# MotorCANInterface.net
KiCad netlist of a schematic drawn in Altium Designer
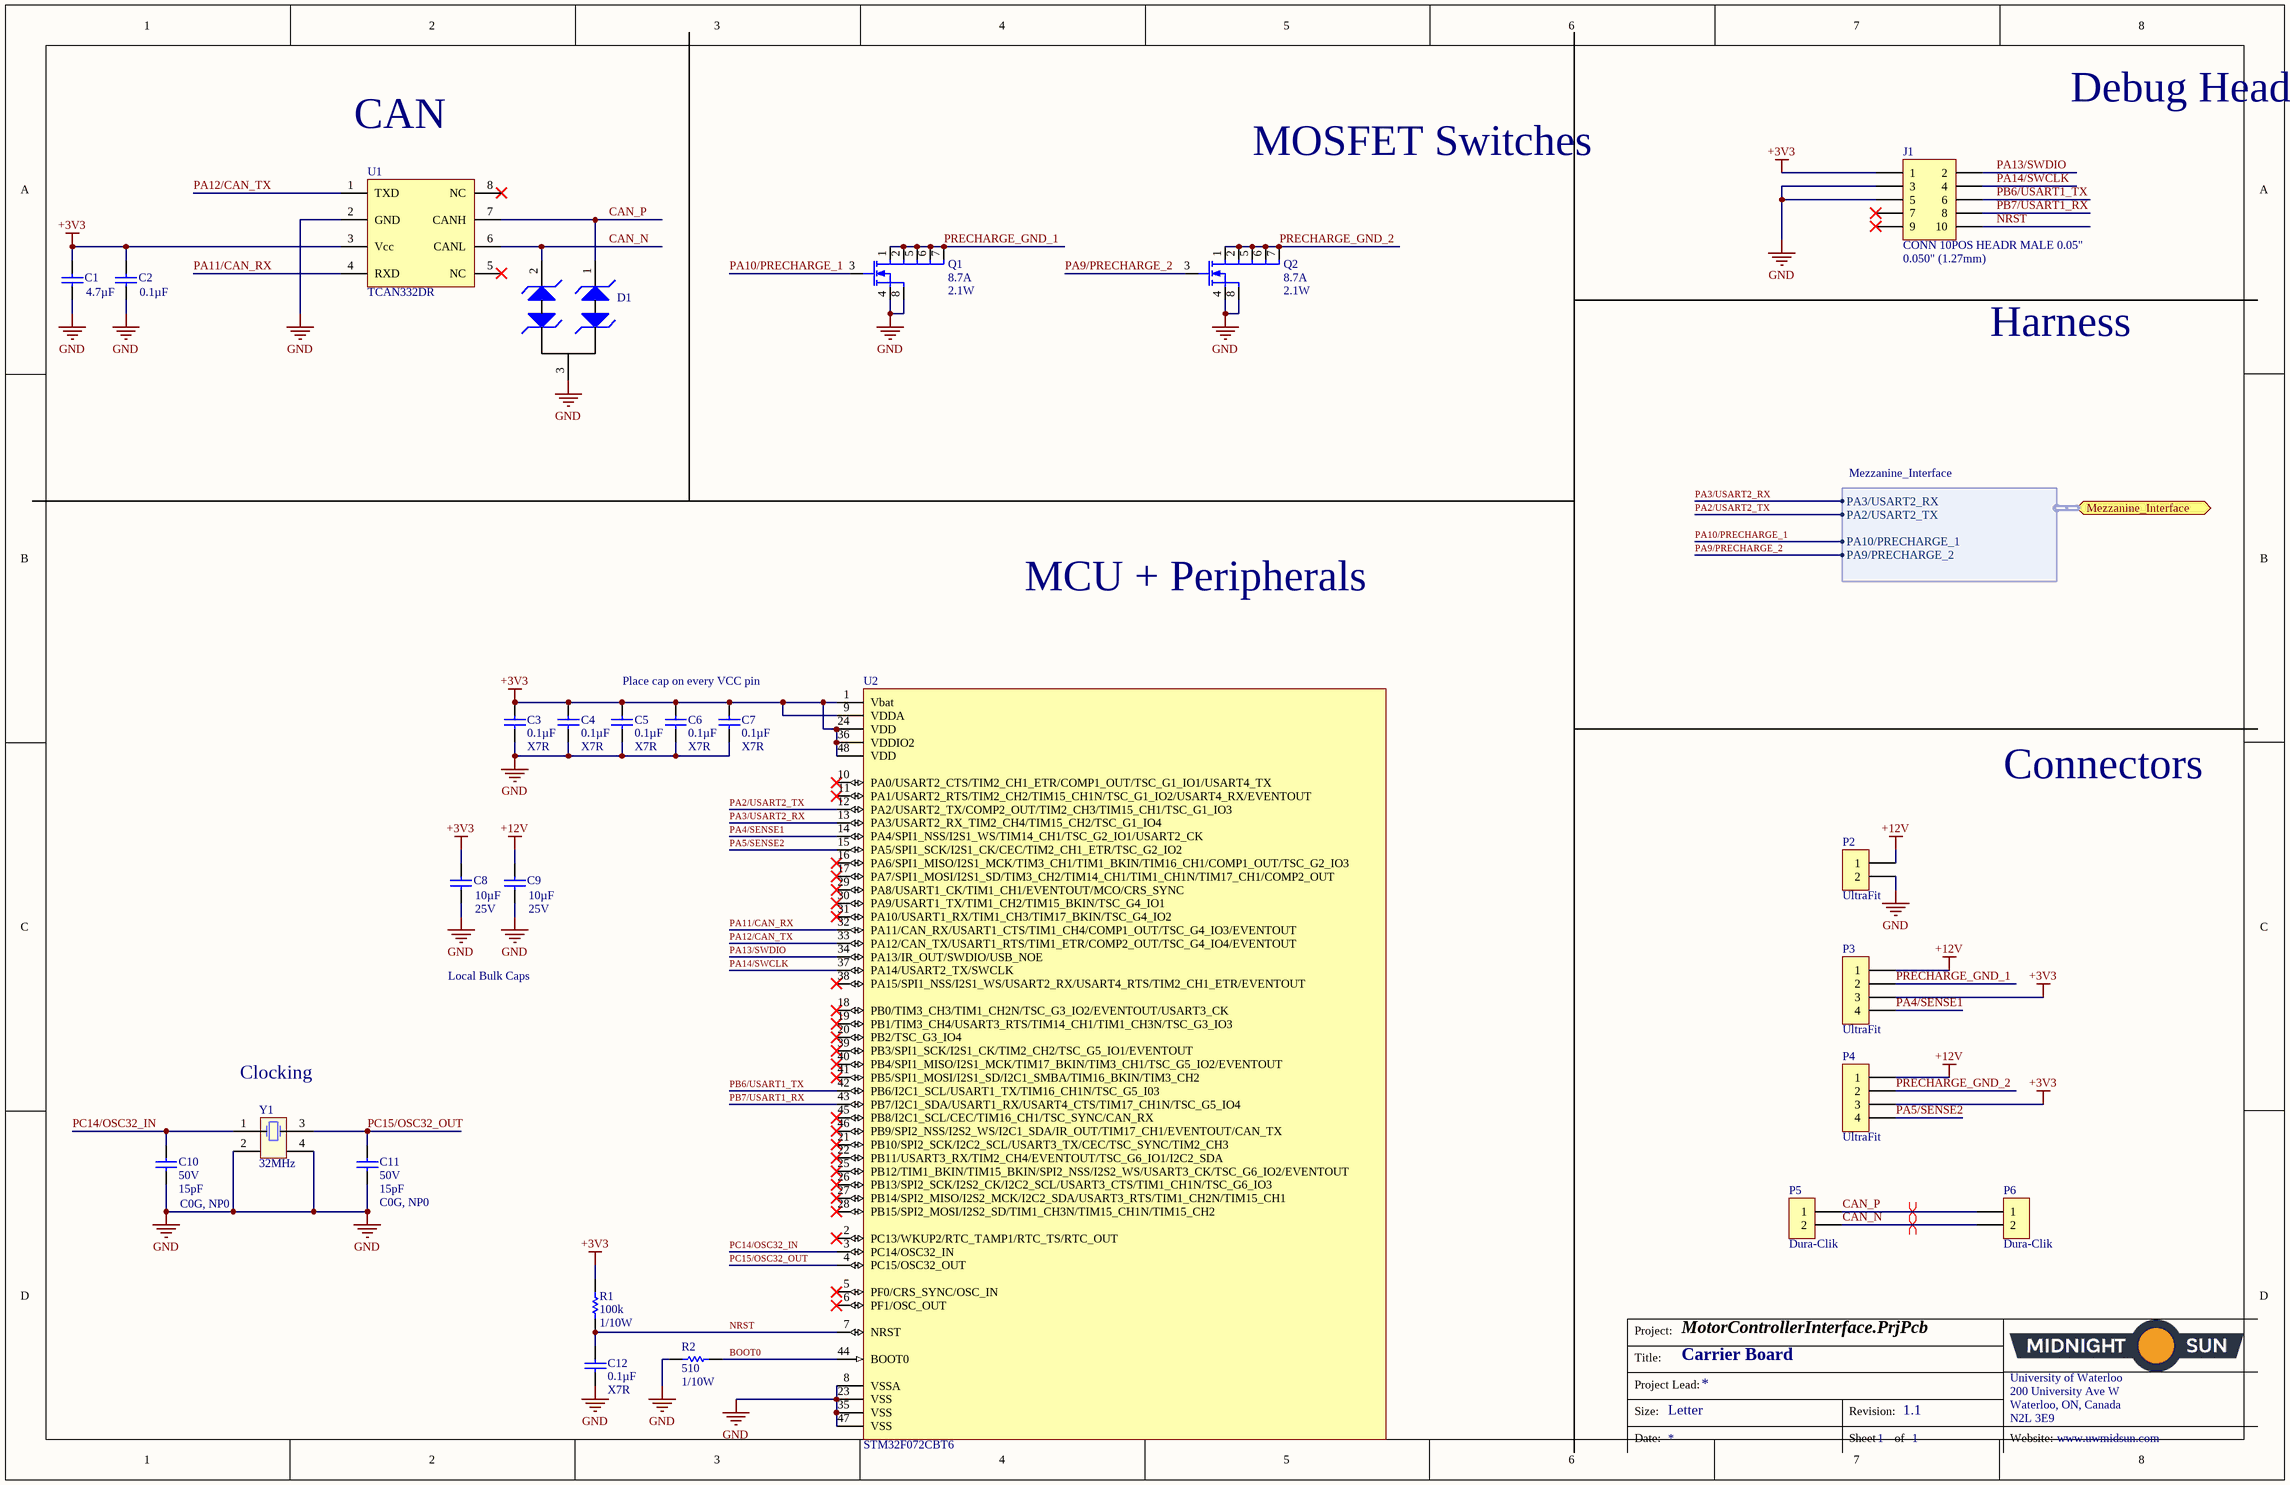
[diagram p0: MotorCANInterface.SchDoc]

(export (version "E")
  (design (tool "Eeschema 10.0.6"))
  (components
    (comp (ref "C1")
      (value "CAP CER 4.7UF 25V 10% X5R 0603")
      (footprint "CAP, 0603")
      (description "4.7µF ±10% 25V Ceramic Capacitor X5R 0603 (1608 Metric)")
      (fields
        (field (name "VOLTAGE") "25V")
        (field (name "TOLERANCE") "±10%")
        (field (name "CAPACITANCE") "4.7µF")
      )
      (libsource (lib "Schematic Diagrams") (part "CAP CER 4.7UF 25V 10% X5R 0603"))
    )
    (comp (ref "C2")
      (value "CAP CER 0.1UF 50V 10% X7R 0603")
      (footprint "CAP, 0603")
      (description "0.10µF ±10% 50V Ceramic Capacitor X7R 0603 (1608 Metric)")
      (fields
        (field (name "VOLTAGE") "50V")
        (field (name "TOLERANCE") "±10%")
        (field (name "CAPACITANCE") "0.1µF")
      )
      (libsource (lib "Schematic Diagrams") (part "CAP CER 0.1UF 50V 10% X7R 0603"))
    )
    (comp (ref "C3")
      (value "CAP CER 0.1UF 50V 10% X7R 0603")
      (footprint "CAP, 0603")
      (description "0.10µF ±10% 50V Ceramic Capacitor X7R 0603 (1608 Metric)")
      (fields
        (field (name "VOLTAGE") "50V")
        (field (name "TOLERANCE") "±10%")
        (field (name "CAPACITANCE") "0.1µF")
        (field (name "TEMPERATURE COEFFICIENT") "X7R")
      )
      (libsource (lib "Schematic Diagrams") (part "CAP CER 0.1UF 50V 10% X7R 0603"))
    )
    (comp (ref "C4")
      (value "CAP CER 0.1UF 50V 10% X7R 0603")
      (footprint "CAP, 0603")
      (description "0.10µF ±10% 50V Ceramic Capacitor X7R 0603 (1608 Metric)")
      (fields
        (field (name "VOLTAGE") "50V")
        (field (name "TOLERANCE") "±10%")
        (field (name "CAPACITANCE") "0.1µF")
        (field (name "TEMPERATURE COEFFICIENT") "X7R")
      )
      (libsource (lib "Schematic Diagrams") (part "CAP CER 0.1UF 50V 10% X7R 0603"))
    )
    (comp (ref "C5")
      (value "CAP CER 0.1UF 50V 10% X7R 0603")
      (footprint "CAP, 0603")
      (description "0.10µF ±10% 50V Ceramic Capacitor X7R 0603 (1608 Metric)")
      (fields
        (field (name "VOLTAGE") "50V")
        (field (name "TOLERANCE") "±10%")
        (field (name "CAPACITANCE") "0.1µF")
        (field (name "TEMPERATURE COEFFICIENT") "X7R")
      )
      (libsource (lib "Schematic Diagrams") (part "CAP CER 0.1UF 50V 10% X7R 0603"))
    )
    (comp (ref "C6")
      (value "CAP CER 0.1UF 50V 10% X7R 0603")
      (footprint "CAP, 0603")
      (description "0.10µF ±10% 50V Ceramic Capacitor X7R 0603 (1608 Metric)")
      (fields
        (field (name "VOLTAGE") "50V")
        (field (name "TOLERANCE") "±10%")
        (field (name "CAPACITANCE") "0.1µF")
        (field (name "TEMPERATURE COEFFICIENT") "X7R")
      )
      (libsource (lib "Schematic Diagrams") (part "CAP CER 0.1UF 50V 10% X7R 0603"))
    )
    (comp (ref "C7")
      (value "CAP CER 0.1UF 50V 10% X7R 0603")
      (footprint "CAP, 0603")
      (description "0.10µF ±10% 50V Ceramic Capacitor X7R 0603 (1608 Metric)")
      (fields
        (field (name "VOLTAGE") "50V")
        (field (name "TOLERANCE") "±10%")
        (field (name "CAPACITANCE") "0.1µF")
        (field (name "TEMPERATURE COEFFICIENT") "X7R")
      )
      (libsource (lib "Schematic Diagrams") (part "CAP CER 0.1UF 50V 10% X7R 0603"))
    )
    (comp (ref "C8")
      (value "CAP CER 10uF 25V 10% X5R 0805")
      (footprint "CAP, 0805")
      (description "10µF ±10% 25V Ceramic Capacitor X5R 0805 (2012 Metric)")
      (fields
        (field (name "MANUFACTURER") "Murata Electronics North America")
        (field (name "MANUFACTURER PART NUMBER") "GRM21BR61E106KA73L")
        (field (name "VOLTAGE - RATED") "25V")
        (field (name "CAPACITANCE") "10µF")
      )
      (libsource (lib "Schematic Diagrams") (part "CAP CER 10uF 25V 10% X5R 0805"))
    )
    (comp (ref "C9")
      (value "CAP CER 10uF 25V 10% X5R 0805")
      (footprint "CAP, 0805")
      (description "10µF ±10% 25V Ceramic Capacitor X5R 0805 (2012 Metric)")
      (fields
        (field (name "MANUFACTURER") "Murata Electronics North America")
        (field (name "MANUFACTURER PART NUMBER") "GRM21BR61E106KA73L")
        (field (name "VOLTAGE - RATED") "25V")
        (field (name "CAPACITANCE") "10µF")
      )
      (libsource (lib "Schematic Diagrams") (part "CAP CER 10uF 25V 10% X5R 0805"))
    )
    (comp (ref "C10")
      (value "CAP CER 15PF 50V ±5% NPO 0603")
      (footprint "CAP, 0603")
      (description "15pF ±5% 50V Ceramic Capacitor C0G, NP0 0603 (1608 Metric)")
      (fields
        (field (name "VOLTAGE") "50V")
        (field (name "TOLERANCE") "±5%")
        (field (name "CAPACITANCE") "15pF")
        (field (name "TEMPERATURE COEFFICIENT") "C0G, NP0")
      )
      (libsource (lib "Schematic Diagrams") (part "CAP CER 15PF 50V ±5% NPO 0603"))
    )
    (comp (ref "C11")
      (value "CAP CER 15PF 50V ±5% NPO 0603")
      (footprint "CAP, 0603")
      (description "15pF ±5% 50V Ceramic Capacitor C0G, NP0 0603 (1608 Metric)")
      (fields
        (field (name "VOLTAGE") "50V")
        (field (name "TOLERANCE") "±5%")
        (field (name "CAPACITANCE") "15pF")
        (field (name "TEMPERATURE COEFFICIENT") "C0G, NP0")
      )
      (libsource (lib "Schematic Diagrams") (part "CAP CER 15PF 50V ±5% NPO 0603"))
    )
    (comp (ref "C12")
      (value "CAP CER 0.1UF 50V 10% X7R 0603")
      (footprint "CAP, 0603")
      (description "0.10µF ±10% 50V Ceramic Capacitor X7R 0603 (1608 Metric)")
      (fields
        (field (name "VOLTAGE") "50V")
        (field (name "TOLERANCE") "±10%")
        (field (name "CAPACITANCE") "0.1µF")
        (field (name "TEMPERATURE COEFFICIENT") "X7R")
      )
      (libsource (lib "Schematic Diagrams") (part "CAP CER 0.1UF 50V 10% X7R 0603"))
    )
    (comp (ref "D1")
      (value "DIODE TVS 24VWM 70VC SOT23")
      (footprint "SOT23")
      (description "TVS DIODE 24VWM 70VC SOT23")
      (libsource (lib "Schematic Diagrams") (part "DIODE TVS 24VWM 70VC SOT23"))
    )
    (comp (ref "J1")
      (value "CONN 10POS HEADR MALE 0.05\"")
      (footprint "CONN, 10POS 0.05\" Debug Header")
      (description "10 Positions Header Connector 0.050\" (1.27mm) Surface Mount Gold")
      (fields (field (name "PITCH - MATING") "0.050\" (1.27mm)"))
      (libsource (lib "Schematic Diagrams") (part "CONN 10POS HEADR MALE 0.05{dblquote}"))
    )
    (comp (ref "P2")
      (value "CONN 2POS ULTRA-FIT 0.138\"")
      (footprint "CONN, 2POS ULTRA-FIT")
      (description "2 Positions Header, Shrouded Connector 0.138\" (3.50mm) Through Hole Gold")
      (fields (field (name "VOLTAGE") "400V") (field (name "SERIES") "UltraFit"))
      (libsource (lib "Schematic Diagrams") (part "CONN 2POS ULTRA-FIT 0.138{dblquote}"))
    )
    (comp (ref "P3")
      (value "CONN 4POS ULTRA-FIT 0.138\"")
      (footprint "CONN, 4POS ULTRA-FIT")
      (description "4 Positions Header Connector 0.138\" (3.50mm) Through Hole Tin")
      (fields (field (name "VOLTAGE") "400V") (field (name "SERIES") "UltraFit"))
      (libsource (lib "Schematic Diagrams") (part "CONN 4POS ULTRA-FIT 0.138{dblquote}"))
    )
    (comp (ref "P4")
      (value "CONN 4POS ULTRA-FIT 0.138\"")
      (footprint "CONN, 4POS ULTRA-FIT")
      (description "4 Positions Header Connector 0.138\" (3.50mm) Through Hole Tin")
      (fields (field (name "VOLTAGE") "400V") (field (name "SERIES") "UltraFit"))
      (libsource (lib "Schematic Diagrams") (part "CONN 4POS ULTRA-FIT 0.138{dblquote}"))
    )
    (comp (ref "P5")
      (value "Dura-Clik")
      (footprint "CONN, 2POS Dura-Click Vertical")
      (description "2 Positions Header, Shrouded Connector 0.079\" (2.00mm) Surface Mount, Vertical Tin")
      (fields
        (field (name "MANUFACTURER") "Molex, LLC")
        (field (name "MANUFACTURER PART NUMBER") "5600200220")
      )
      (libsource (lib "") (part "CONN 2POS DURA-CLIK 0.079{dblquote} VERT_1"))
    )
    (comp (ref "P6")
      (value "Dura-Clik")
      (footprint "CONN, 2POS Dura-Click Vertical")
      (description "2 Positions Header, Shrouded Connector 0.079\" (2.00mm) Surface Mount, Vertical Tin")
      (fields
        (field (name "MANUFACTURER") "Molex, LLC")
        (field (name "MANUFACTURER PART NUMBER") "5600200220")
      )
      (libsource (lib "Schematic Diagrams") (part "CONN 2POS DURA-CLIK 0.079{dblquote} VERT"))
    )
    (comp (ref "Q1")
      (value "MOSFET N-CH 30V 8.7A 2.1W 6-PQFN (2x2)")
      (footprint "MOSFET N-CH 30V 12A 2mmx2mm PQFN")
      (fields
        (field (name "CURRENT - CONTINUOUS DRAIN (ID) @ 25°C") "8.7A")
        (field (name "POWER DISSIPATION (MAX)") "2.1W")
      )
      (libsource (lib "Schematic Diagrams") (part "MOSFET N-CH 30V 8.7A 2.1W 6-PQFN (2x2)"))
    )
    (comp (ref "Q2")
      (value "MOSFET N-CH 30V 8.7A 2.1W 6-PQFN (2x2)")
      (footprint "MOSFET N-CH 30V 12A 2mmx2mm PQFN")
      (fields
        (field (name "CURRENT - CONTINUOUS DRAIN (ID) @ 25°C") "8.7A")
        (field (name "POWER DISSIPATION (MAX)") "2.1W")
      )
      (libsource (lib "Schematic Diagrams") (part "MOSFET N-CH 30V 8.7A 2.1W 6-PQFN (2x2)"))
    )
    (comp (ref "R1")
      (value "RES 100K OHM 5% 1/8W 0603")
      (footprint "RES, 0603")
      (description "RES SMD 100K OHM 5% 1/10W 0603")
      (fields
        (field (name "TOLERANCE") "±5%")
        (field (name "RESISTANCE") "100k")
        (field (name "POWER") "1/10W")
      )
      (libsource (lib "Schematic Diagrams") (part "RES 100K OHM 5% 1/8W 0603"))
    )
    (comp (ref "R2")
      (value "RES 510 OHM 5% 1/10W 0603")
      (footprint "RES, 0603")
      (description "RES SMD 510 OHM 5% 1/10W 0603")
      (fields
        (field (name "TOLERANCE") "±5%")
        (field (name "RESISTANCE") "510")
        (field (name "POWER") "1/10W")
      )
      (libsource (lib "Schematic Diagrams") (part "RES 510 OHM 5% 1/10W 0603"))
    )
    (comp (ref "U1")
      (value "IC CAN Tranceiver TCAN332DR")
      (footprint "TSOP65P280X145-8N")
      (description "1/1 Transceiver CAN 8-SOIC")
      (fields
        (field (name "DIGIKEY PART NUMBER") "296-43711-1-ND")
        (field (name "MANUFACTURER PART NUMBER") "TCAN332DR")
      )
      (libsource (lib "Schematic Diagrams") (part "IC CAN Tranceiver TCAN332DR"))
    )
    (comp (ref "U2")
      (value "IC MCU 32BIT 128KB FLASH 48LQFP")
      (footprint "TSQFP50P890X890X160-48M")
      (description "ARM® Cortex®-M0 STM32 F0 Microcontroller IC 32-Bit 48MHz 128KB (128K x 8) FLASH 48-LQFP (7x7)")
      (fields (field (name "MANUFACTURER PART NUMBER 1") "STM32F072CBT6"))
      (libsource (lib "Schematic Diagrams") (part "IC MCU 32BIT 128KB FLASH 48LQFP"))
    )
    (comp (ref "Y1")
      (value "CRYSTAL 32 MHz 8pF 4-SMD")
      (footprint "CX2520DB CRYSTAL")
      (description "32MHz ±15ppm Crystal 8pF 50 Ohm -40°C ~ 85°C AEC-Q200 Surface Mount 4-SMD, No Lead")
      (fields (field (name "FREQUENCY") "32MHz"))
      (libsource (lib "Schematic Diagrams") (part "CRYSTAL 32 MHz 8pF 4-SMD"))
    )
  )
  (nets
    (net (code "2") (name "+3V3") (class "Default")
      (node (ref "C1") (pin "1") (pinfunction "1_1") (pintype "passive"))
      (node (ref "C2") (pin "1") (pinfunction "1_1") (pintype "passive"))
      (node (ref "C3") (pin "1") (pinfunction "1_1") (pintype "passive"))
      (node (ref "C4") (pin "1") (pinfunction "1_1") (pintype "passive"))
      (node (ref "C5") (pin "1") (pinfunction "1_1") (pintype "passive"))
      (node (ref "C6") (pin "1") (pinfunction "1_1") (pintype "passive"))
      (node (ref "C7") (pin "1") (pinfunction "1_1") (pintype "passive"))
      (node (ref "C8") (pin "1") (pinfunction "1_1") (pintype "passive"))
      (node (ref "J1") (pin "1") (pinfunction "1_1") (pintype "passive"))
      (node (ref "P3") (pin "3") (pinfunction "3_3") (pintype "passive"))
      (node (ref "P4") (pin "3") (pinfunction "3_3") (pintype "passive"))
      (node (ref "R1") (pin "1") (pinfunction "1_1") (pintype "passive"))
      (node (ref "U1") (pin "3") (pinfunction "Vcc_3") (pintype "passive"))
      (node (ref "U2") (pin "1") (pinfunction "Vbat_1") (pintype "power_in"))
      (node (ref "U2") (pin "24") (pinfunction "VDD_24") (pintype "power_in"))
      (node (ref "U2") (pin "36") (pinfunction "VDDIO2_36") (pintype "power_in"))
      (node (ref "U2") (pin "48") (pinfunction "VDD_48") (pintype "power_in"))
      (node (ref "U2") (pin "9") (pinfunction "VDDA_9") (pintype "power_in"))
    )
    (net (code "3") (name "+12V") (class "Default")
      (node (ref "C9") (pin "1") (pinfunction "1_1") (pintype "passive"))
      (node (ref "P2") (pin "1") (pinfunction "1_1") (pintype "passive"))
      (node (ref "P3") (pin "1") (pinfunction "1_1") (pintype "passive"))
      (node (ref "P4") (pin "1") (pinfunction "1_1") (pintype "passive"))
    )
    (net (code "4") (name "/BOOT0") (class "Default")
      (node (ref "R2") (pin "2") (pinfunction "2_2") (pintype "passive"))
      (node (ref "U2") (pin "44") (pinfunction "BOOT0_44") (pintype "input"))
    )
    (net (code "5") (name "/CAN_N") (class "Default")
      (node (ref "D1") (pin "2") (pinfunction "Cathode2_2") (pintype "passive"))
      (node (ref "P5") (pin "2") (pinfunction "2_2") (pintype "passive"))
      (node (ref "P6") (pin "2") (pinfunction "2_2") (pintype "passive"))
      (node (ref "U1") (pin "6") (pinfunction "CANL_6") (pintype "passive"))
    )
    (net (code "6") (name "/CAN_P") (class "Default")
      (node (ref "D1") (pin "1") (pinfunction "Cathode1_1") (pintype "passive"))
      (node (ref "P5") (pin "1") (pinfunction "1_1") (pintype "passive"))
      (node (ref "P6") (pin "1") (pinfunction "1_1") (pintype "passive"))
      (node (ref "U1") (pin "7") (pinfunction "CANH_7") (pintype "passive"))
    )
    (net (code "7") (name "/NRST") (class "Default")
      (node (ref "C12") (pin "1") (pinfunction "1_1") (pintype "passive"))
      (node (ref "J1") (pin "10") (pinfunction "10_10") (pintype "passive"))
      (node (ref "R1") (pin "2") (pinfunction "2_2") (pintype "passive"))
      (node (ref "U2") (pin "7") (pinfunction "NRST_7") (pintype "bidirectional"))
    )
    (net (code "8") (name "/PA2{slash}USART2_TX") (class "Default")
      (node (ref "U2") (pin "12") (pinfunction "PA2/USART2_TX/COMP2_OUT/TIM2_CH3/TIM15_CH1/TSC_G1_IO3_12") (pintype "bidirectional"))
    )
    (net (code "9") (name "/PA3{slash}USART2_RX") (class "Default")
      (node (ref "U2") (pin "13") (pinfunction "PA3/USART2_RX_TIM2_CH4/TIM15_CH2/TSC_G1_IO4_13") (pintype "bidirectional"))
    )
    (net (code "10") (name "/PA4{slash}SENSE1") (class "Default")
      (node (ref "P3") (pin "4") (pinfunction "4_4") (pintype "passive"))
      (node (ref "U2") (pin "14") (pinfunction "PA4/SPI1_NSS/I2S1_WS/TIM14_CH1/TSC_G2_IO1/USART2_CK_14") (pintype "bidirectional"))
    )
    (net (code "11") (name "/PA5{slash}SENSE2") (class "Default")
      (node (ref "P4") (pin "4") (pinfunction "4_4") (pintype "passive"))
      (node (ref "U2") (pin "15") (pinfunction "PA5/SPI1_SCK/I2S1_CK/CEC/TIM2_CH1_ETR/TSC_G2_IO2_15") (pintype "bidirectional"))
    )
    (net (code "12") (name "/PA9{slash}PRECHARGE_2") (class "Default")
      (node (ref "Q2") (pin "3") (pinfunction "G_3") (pintype "passive"))
    )
    (net (code "13") (name "/PA10{slash}PRECHARGE_1") (class "Default")
      (node (ref "Q1") (pin "3") (pinfunction "G_3") (pintype "passive"))
    )
    (net (code "14") (name "/PA11{slash}CAN_RX") (class "Default")
      (node (ref "U1") (pin "4") (pinfunction "RXD_4") (pintype "passive"))
      (node (ref "U2") (pin "32") (pinfunction "PA11/CAN_RX/USART1_CTS/TIM1_CH4/COMP1_OUT/TSC_G4_IO3/EVENTOUT_32") (pintype "bidirectional"))
    )
    (net (code "15") (name "/PA12{slash}CAN_TX") (class "Default")
      (node (ref "U1") (pin "1") (pinfunction "TXD_1") (pintype "passive"))
      (node (ref "U2") (pin "33") (pinfunction "PA12/CAN_TX/USART1_RTS/TIM1_ETR/COMP2_OUT/TSC_G4_IO4/EVENTOUT_33") (pintype "bidirectional"))
    )
    (net (code "16") (name "/PA13{slash}SWDIO") (class "Default")
      (node (ref "J1") (pin "2") (pinfunction "2_2") (pintype "passive"))
      (node (ref "U2") (pin "34") (pinfunction "PA13/IR_OUT/SWDIO/USB_NOE_34") (pintype "bidirectional"))
    )
    (net (code "17") (name "/PA14{slash}SWCLK") (class "Default")
      (node (ref "J1") (pin "4") (pinfunction "4_4") (pintype "passive"))
      (node (ref "U2") (pin "37") (pinfunction "PA14/USART2_TX/SWCLK_37") (pintype "bidirectional"))
    )
    (net (code "18") (name "/PB6{slash}USART1_TX") (class "Default")
      (node (ref "J1") (pin "6") (pinfunction "6_6") (pintype "passive"))
      (node (ref "U2") (pin "42") (pinfunction "PB6/I2C1_SCL/USART1_TX/TIM16_CH1N/TSC_G5_I03_42") (pintype "bidirectional"))
    )
    (net (code "19") (name "/PB7{slash}USART1_RX") (class "Default")
      (node (ref "J1") (pin "8") (pinfunction "8_8") (pintype "passive"))
      (node (ref "U2") (pin "43") (pinfunction "PB7/I2C1_SDA/USART1_RX/USART4_CTS/TIM17_CH1N/TSC_G5_IO4_43") (pintype "bidirectional"))
    )
    (net (code "20") (name "/PC14{slash}OSC32_IN") (class "Default")
      (node (ref "C10") (pin "1") (pinfunction "1_1") (pintype "passive"))
      (node (ref "U2") (pin "3") (pinfunction "PC14/OSC32_IN_3") (pintype "bidirectional"))
      (node (ref "Y1") (pin "1") (pinfunction "OSC1_1") (pintype "passive"))
    )
    (net (code "21") (name "/PC15{slash}OSC32_OUT") (class "Default")
      (node (ref "C11") (pin "1") (pinfunction "1_1") (pintype "passive"))
      (node (ref "U2") (pin "4") (pinfunction "PC15/OSC32_OUT_4") (pintype "bidirectional"))
      (node (ref "Y1") (pin "3") (pinfunction "OSC2_3") (pintype "passive"))
    )
    (net (code "22") (name "/PRECHARGE_GND_1") (class "Default")
      (node (ref "P3") (pin "2") (pinfunction "2_2") (pintype "passive"))
      (node (ref "Q1") (pin "1") (pinfunction "D_1") (pintype "passive"))
      (node (ref "Q1") (pin "2") (pinfunction "D_2") (pintype "passive"))
      (node (ref "Q1") (pin "5") (pinfunction "D_5") (pintype "passive"))
      (node (ref "Q1") (pin "6") (pinfunction "D_6") (pintype "passive"))
      (node (ref "Q1") (pin "7") (pinfunction "D_7") (pintype "passive"))
    )
    (net (code "23") (name "/PRECHARGE_GND_2") (class "Default")
      (node (ref "P4") (pin "2") (pinfunction "2_2") (pintype "passive"))
      (node (ref "Q2") (pin "1") (pinfunction "D_1") (pintype "passive"))
      (node (ref "Q2") (pin "2") (pinfunction "D_2") (pintype "passive"))
      (node (ref "Q2") (pin "5") (pinfunction "D_5") (pintype "passive"))
      (node (ref "Q2") (pin "6") (pinfunction "D_6") (pintype "passive"))
      (node (ref "Q2") (pin "7") (pinfunction "D_7") (pintype "passive"))
    )
    (net (code "25") (name "GND") (class "Default")
      (node (ref "C1") (pin "2") (pinfunction "2_2") (pintype "passive"))
      (node (ref "C10") (pin "2") (pinfunction "2_2") (pintype "passive"))
      (node (ref "C11") (pin "2") (pinfunction "2_2") (pintype "passive"))
      (node (ref "C12") (pin "2") (pinfunction "2_2") (pintype "passive"))
      (node (ref "C2") (pin "2") (pinfunction "2_2") (pintype "passive"))
      (node (ref "C3") (pin "2") (pinfunction "2_2") (pintype "passive"))
      (node (ref "C4") (pin "2") (pinfunction "2_2") (pintype "passive"))
      (node (ref "C5") (pin "2") (pinfunction "2_2") (pintype "passive"))
      (node (ref "C6") (pin "2") (pinfunction "2_2") (pintype "passive"))
      (node (ref "C7") (pin "2") (pinfunction "2_2") (pintype "passive"))
      (node (ref "C8") (pin "2") (pinfunction "2_2") (pintype "passive"))
      (node (ref "C9") (pin "2") (pinfunction "2_2") (pintype "passive"))
      (node (ref "D1") (pin "3") (pinfunction "Common_Cathode_3") (pintype "power_in"))
      (node (ref "J1") (pin "3") (pinfunction "3_3") (pintype "passive"))
      (node (ref "J1") (pin "5") (pinfunction "5_5") (pintype "passive"))
      (node (ref "P2") (pin "2") (pinfunction "2_2") (pintype "passive"))
      (node (ref "Q1") (pin "4") (pinfunction "S_4") (pintype "passive"))
      (node (ref "Q1") (pin "8") (pinfunction "S_8") (pintype "passive"))
      (node (ref "Q2") (pin "4") (pinfunction "S_4") (pintype "passive"))
      (node (ref "Q2") (pin "8") (pinfunction "S_8") (pintype "passive"))
      (node (ref "R2") (pin "1") (pinfunction "1_1") (pintype "passive"))
      (node (ref "U1") (pin "2") (pinfunction "GND_2") (pintype "passive"))
      (node (ref "U2") (pin "23") (pinfunction "VSS_23") (pintype "power_in"))
      (node (ref "U2") (pin "35") (pinfunction "VSS_35") (pintype "power_in"))
      (node (ref "U2") (pin "47") (pinfunction "VSS_47") (pintype "power_in"))
      (node (ref "U2") (pin "8") (pinfunction "VSSA_8") (pintype "power_in"))
      (node (ref "Y1") (pin "2") (pinfunction "2_2") (pintype "passive"))
      (node (ref "Y1") (pin "4") (pinfunction "3_4") (pintype "passive"))
    )
    (net (code "26") (name "unconnected-(J1-Pad7)") (class "Default")
      (node (ref "J1") (pin "7") (pinfunction "7_7") (pintype "passive+no_connect"))
    )
    (net (code "27") (name "unconnected-(J1-Pad9)") (class "Default")
      (node (ref "J1") (pin "9") (pinfunction "9_9") (pintype "passive+no_connect"))
    )
    (net (code "28") (name "unconnected-(U1-NC-Pad5)") (class "Default")
      (node (ref "U1") (pin "5") (pinfunction "NC_5") (pintype "passive+no_connect"))
    )
    (net (code "29") (name "unconnected-(U1-NC-Pad8)") (class "Default")
      (node (ref "U1") (pin "8") (pinfunction "NC_8") (pintype "passive+no_connect"))
    )
    (net (code "30") (name "unconnected-(U2-PA0{slash}USART2_CTS{slash}TIM2_CH1_ETR{slash}COMP1_OUT{slash}TSC_G1_IO1{slash}USART4_TX-Pad10)") (class "Default")
      (node (ref "U2") (pin "10") (pinfunction "PA0/USART2_CTS/TIM2_CH1_ETR/COMP1_OUT/TSC_G1_IO1/USART4_TX_10") (pintype "bidirectional+no_connect"))
    )
    (net (code "31") (name "unconnected-(U2-PA1{slash}USART2_RTS{slash}TIM2_CH2{slash}TIM15_CH1N{slash}TSC_G1_IO2{slash}USART4_RX{slash}EVENTOUT-Pad11)") (class "Default")
      (node (ref "U2") (pin "11") (pinfunction "PA1/USART2_RTS/TIM2_CH2/TIM15_CH1N/TSC_G1_IO2/USART4_RX/EVENTOUT_11") (pintype "bidirectional+no_connect"))
    )
    (net (code "32") (name "unconnected-(U2-PA6{slash}SPI1_MISO{slash}I2S1_MCK{slash}TIM3_CH1{slash}TIM1_BKIN{slash}TIM16_CH1{slash}COMP1_OUT{slash}TSC_G2_IO3-Pad16)") (class "Default")
      (node (ref "U2") (pin "16") (pinfunction "PA6/SPI1_MISO/I2S1_MCK/TIM3_CH1/TIM1_BKIN/TIM16_CH1/COMP1_OUT/TSC_G2_IO3_16") (pintype "bidirectional+no_connect"))
    )
    (net (code "33") (name "unconnected-(U2-PA7{slash}SPI1_MOSI{slash}I2S1_SD{slash}TIM3_CH2{slash}TIM14_CH1{slash}TIM1_CH1N{slash}TIM17_CH1{slash}COMP2_OUT-Pad17)") (class "Default")
      (node (ref "U2") (pin "17") (pinfunction "PA7/SPI1_MOSI/I2S1_SD/TIM3_CH2/TIM14_CH1/TIM1_CH1N/TIM17_CH1/COMP2_OUT_17") (pintype "bidirectional+no_connect"))
    )
    (net (code "34") (name "unconnected-(U2-PA8{slash}USART1_CK{slash}TIM1_CH1{slash}EVENTOUT{slash}MCO{slash}CRS_SYNC-Pad29)") (class "Default")
      (node (ref "U2") (pin "29") (pinfunction "PA8/USART1_CK/TIM1_CH1/EVENTOUT/MCO/CRS_SYNC_29") (pintype "bidirectional+no_connect"))
    )
    (net (code "35") (name "unconnected-(U2-PA9{slash}USART1_TX{slash}TIM1_CH2{slash}TIM15_BKIN{slash}TSC_G4_IO1-Pad30)") (class "Default")
      (node (ref "U2") (pin "30") (pinfunction "PA9/USART1_TX/TIM1_CH2/TIM15_BKIN/TSC_G4_IO1_30") (pintype "bidirectional+no_connect"))
    )
    (net (code "36") (name "unconnected-(U2-PA10{slash}USART1_RX{slash}TIM1_CH3{slash}TIM17_BKIN{slash}TSC_G4_IO2-Pad31)") (class "Default")
      (node (ref "U2") (pin "31") (pinfunction "PA10/USART1_RX/TIM1_CH3/TIM17_BKIN/TSC_G4_IO2_31") (pintype "bidirectional+no_connect"))
    )
    (net (code "37") (name "unconnected-(U2-PA15{slash}SPI1_NSS{slash}I2S1_WS{slash}USART2_RX{slash}USART4_RTS{slash}TIM2_CH1_ETR{slash}EVENTOUT-Pad38)") (class "Default")
      (node (ref "U2") (pin "38") (pinfunction "PA15/SPI1_NSS/I2S1_WS/USART2_RX/USART4_RTS/TIM2_CH1_ETR/EVENTOUT_38") (pintype "bidirectional+no_connect"))
    )
    (net (code "38") (name "unconnected-(U2-PB0{slash}TIM3_CH3{slash}TIM1_CH2N{slash}TSC_G3_IO2{slash}EVENTOUT{slash}USART3_CK-Pad18)") (class "Default")
      (node (ref "U2") (pin "18") (pinfunction "PB0/TIM3_CH3/TIM1_CH2N/TSC_G3_IO2/EVENTOUT/USART3_CK_18") (pintype "bidirectional+no_connect"))
    )
    (net (code "39") (name "unconnected-(U2-PB1{slash}TIM3_CH4{slash}USART3_RTS{slash}TIM14_CH1{slash}TIM1_CH3N{slash}TSC_G3_IO3-Pad19)") (class "Default")
      (node (ref "U2") (pin "19") (pinfunction "PB1/TIM3_CH4/USART3_RTS/TIM14_CH1/TIM1_CH3N/TSC_G3_IO3_19") (pintype "bidirectional+no_connect"))
    )
    (net (code "40") (name "unconnected-(U2-PB2{slash}TSC_G3_IO4-Pad20)") (class "Default")
      (node (ref "U2") (pin "20") (pinfunction "PB2/TSC_G3_IO4_20") (pintype "bidirectional+no_connect"))
    )
    (net (code "41") (name "unconnected-(U2-PB3{slash}SPI1_SCK{slash}I2S1_CK{slash}TIM2_CH2{slash}TSC_G5_IO1{slash}EVENTOUT-Pad39)") (class "Default")
      (node (ref "U2") (pin "39") (pinfunction "PB3/SPI1_SCK/I2S1_CK/TIM2_CH2/TSC_G5_IO1/EVENTOUT_39") (pintype "bidirectional+no_connect"))
    )
    (net (code "42") (name "unconnected-(U2-PB4{slash}SPI1_MISO{slash}I2S1_MCK{slash}TIM17_BKIN{slash}TIM3_CH1{slash}TSC_G5_IO2{slash}EVENTOUT-Pad40)") (class "Default")
      (node (ref "U2") (pin "40") (pinfunction "PB4/SPI1_MISO/I2S1_MCK/TIM17_BKIN/TIM3_CH1/TSC_G5_IO2/EVENTOUT_40") (pintype "bidirectional+no_connect"))
    )
    (net (code "43") (name "unconnected-(U2-PB5{slash}SPI1_MOSI{slash}I2S1_SD{slash}I2C1_SMBA{slash}TIM16_BKIN{slash}TIM3_CH2-Pad41)") (class "Default")
      (node (ref "U2") (pin "41") (pinfunction "PB5/SPI1_MOSI/I2S1_SD/I2C1_SMBA/TIM16_BKIN/TIM3_CH2_41") (pintype "bidirectional+no_connect"))
    )
    (net (code "44") (name "unconnected-(U2-PB8{slash}I2C1_SCL{slash}CEC{slash}TIM16_CH1{slash}TSC_SYNC{slash}CAN_RX-Pad45)") (class "Default")
      (node (ref "U2") (pin "45") (pinfunction "PB8/I2C1_SCL/CEC/TIM16_CH1/TSC_SYNC/CAN_RX_45") (pintype "bidirectional+no_connect"))
    )
    (net (code "45") (name "unconnected-(U2-PB9{slash}SPI2_NSS{slash}I2S2_WS{slash}I2C1_SDA{slash}IR_OUT{slash}TIM17_CH1{slash}EVENTOUT{slash}CAN_TX-Pad46)") (class "Default")
      (node (ref "U2") (pin "46") (pinfunction "PB9/SPI2_NSS/I2S2_WS/I2C1_SDA/IR_OUT/TIM17_CH1/EVENTOUT/CAN_TX_46") (pintype "bidirectional+no_connect"))
    )
    (net (code "46") (name "unconnected-(U2-PB10{slash}SPI2_SCK{slash}I2C2_SCL{slash}USART3_TX{slash}CEC{slash}TSC_SYNC{slash}TIM2_CH3-Pad21)") (class "Default")
      (node (ref "U2") (pin "21") (pinfunction "PB10/SPI2_SCK/I2C2_SCL/USART3_TX/CEC/TSC_SYNC/TIM2_CH3_21") (pintype "bidirectional+no_connect"))
    )
    (net (code "47") (name "unconnected-(U2-PB11{slash}USART3_RX{slash}TIM2_CH4{slash}EVENTOUT{slash}TSC_G6_IO1{slash}I2C2_SDA-Pad22)") (class "Default")
      (node (ref "U2") (pin "22") (pinfunction "PB11/USART3_RX/TIM2_CH4/EVENTOUT/TSC_G6_IO1/I2C2_SDA_22") (pintype "bidirectional+no_connect"))
    )
    (net (code "48") (name "unconnected-(U2-PB12{slash}TIM1_BKIN{slash}TIM15_BKIN{slash}SPI2_NSS{slash}I2S2_WS{slash}USART3_CK{slash}TSC_G6_IO2{slash}EVENTOUT-Pad25)") (class "Default")
      (node (ref "U2") (pin "25") (pinfunction "PB12/TIM1_BKIN/TIM15_BKIN/SPI2_NSS/I2S2_WS/USART3_CK/TSC_G6_IO2/EVENTOUT_25") (pintype "bidirectional+no_connect"))
    )
    (net (code "49") (name "unconnected-(U2-PB13{slash}SPI2_SCK{slash}I2S2_CK{slash}I2C2_SCL{slash}USART3_CTS{slash}TIM1_CH1N{slash}TSC_G6_IO3-Pad26)") (class "Default")
      (node (ref "U2") (pin "26") (pinfunction "PB13/SPI2_SCK/I2S2_CK/I2C2_SCL/USART3_CTS/TIM1_CH1N/TSC_G6_IO3_26") (pintype "bidirectional+no_connect"))
    )
    (net (code "50") (name "unconnected-(U2-PB14{slash}SPI2_MISO{slash}I2S2_MCK{slash}I2C2_SDA{slash}USART3_RTS{slash}TIM1_CH2N{slash}TIM15_CH1-Pad27)") (class "Default")
      (node (ref "U2") (pin "27") (pinfunction "PB14/SPI2_MISO/I2S2_MCK/I2C2_SDA/USART3_RTS/TIM1_CH2N/TIM15_CH1_27") (pintype "bidirectional+no_connect"))
    )
    (net (code "51") (name "unconnected-(U2-PB15{slash}SPI2_MOSI{slash}I2S2_SD{slash}TIM1_CH3N{slash}TIM15_CH1N{slash}TIM15_CH2-Pad28)") (class "Default")
      (node (ref "U2") (pin "28") (pinfunction "PB15/SPI2_MOSI/I2S2_SD/TIM1_CH3N/TIM15_CH1N/TIM15_CH2_28") (pintype "bidirectional+no_connect"))
    )
    (net (code "52") (name "unconnected-(U2-PC13{slash}WKUP2{slash}RTC_TAMP1{slash}RTC_TS{slash}RTC_OUT-Pad2)") (class "Default")
      (node (ref "U2") (pin "2") (pinfunction "PC13/WKUP2/RTC_TAMP1/RTC_TS/RTC_OUT_2") (pintype "bidirectional+no_connect"))
    )
    (net (code "53") (name "unconnected-(U2-PF0{slash}CRS_SYNC{slash}OSC_IN-Pad5)") (class "Default")
      (node (ref "U2") (pin "5") (pinfunction "PF0/CRS_SYNC/OSC_IN_5") (pintype "bidirectional+no_connect"))
    )
    (net (code "54") (name "unconnected-(U2-PF1{slash}OSC_OUT-Pad6)") (class "Default")
      (node (ref "U2") (pin "6") (pinfunction "PF1/OSC_OUT_6") (pintype "bidirectional+no_connect"))
    )
  )
)
